# 07_AD9363.net
KiCad netlist of a schematic drawn in Altium Designer
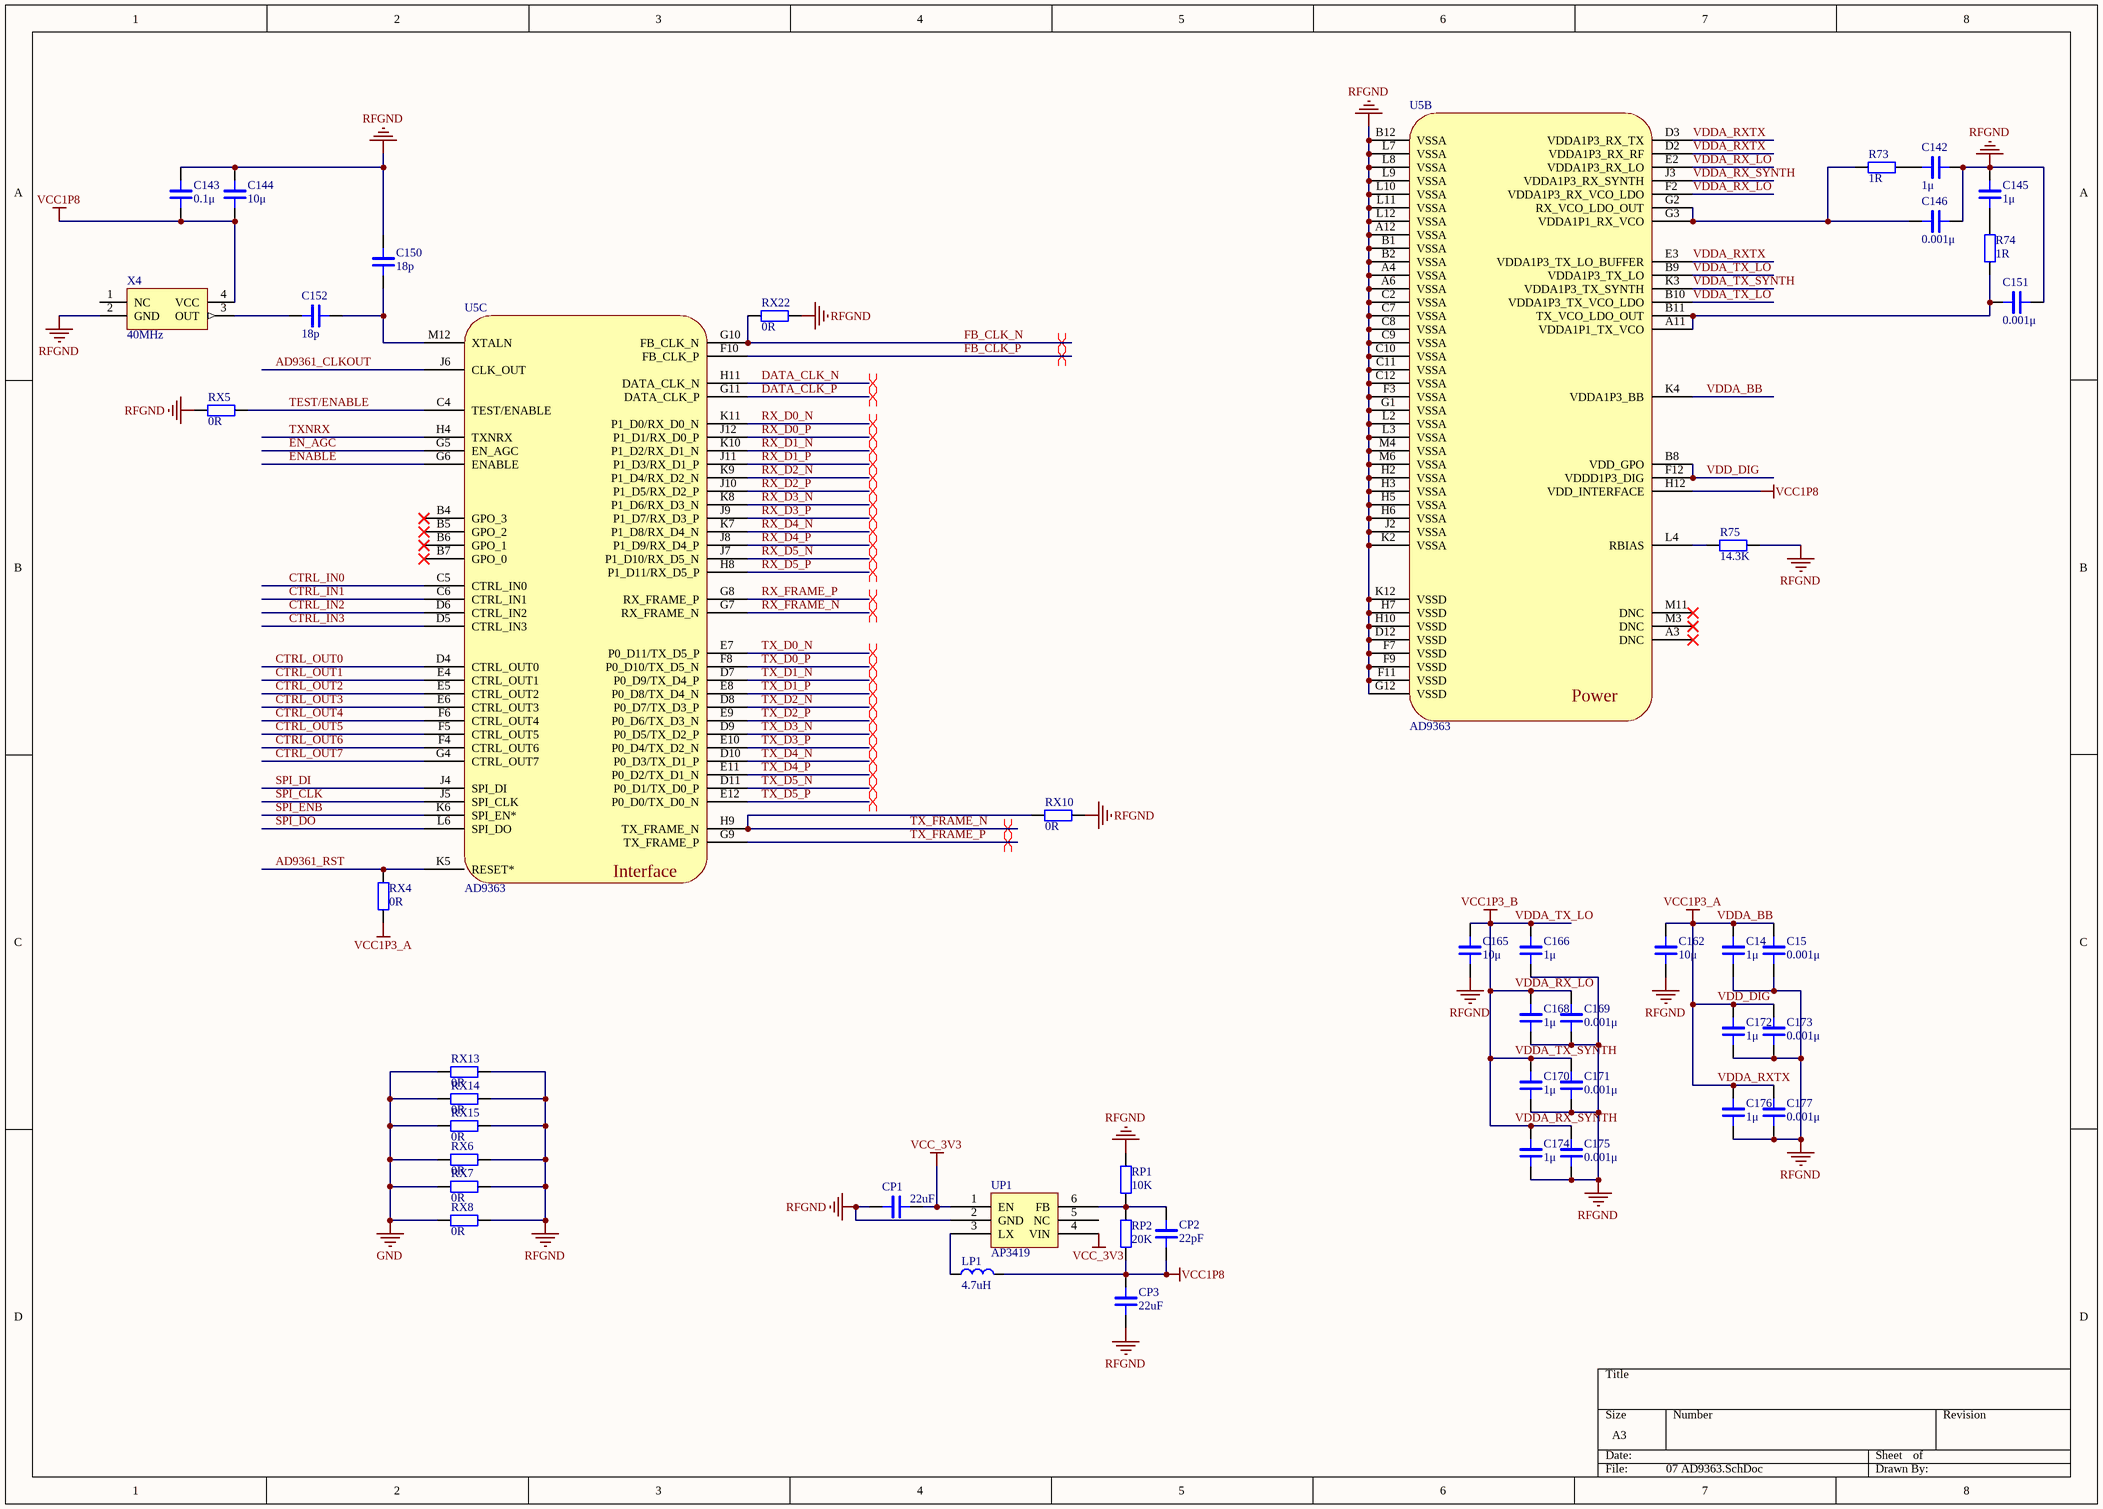
[diagram p0: 07 AD9363.SchDoc]

(export (version "E")
  (design (tool "Eeschema 10.0.6"))
  (components
    (comp (ref "C14")
      (value "1μ")
      (footprint "LC-0402_C")
      (description "Capacitor")
      (libsource (lib "DDR3_xc7z010-clg400") (part "CAP_1"))
    )
    (comp (ref "C15")
      (value "0.001μ")
      (footprint "LC-0402_C")
      (description "Capacitor")
      (libsource (lib "DDR3_xc7z010-clg400") (part "CAP_1"))
    )
    (comp (ref "C142")
      (value "1μ")
      (footprint "LC-0402_C")
      (description "Capacitor")
      (libsource (lib "DDR3_xc7z010-clg400") (part "CAP_2"))
    )
    (comp (ref "C143")
      (value "0.1μ")
      (footprint "LC-0402_C")
      (description "Capacitor")
      (libsource (lib "DDR3_xc7z010-clg400") (part "CAP_2"))
    )
    (comp (ref "C144")
      (value "10μ")
      (footprint "LC-0402_C")
      (description "Capacitor")
      (libsource (lib "DDR3_xc7z010-clg400") (part "CAP_2"))
    )
    (comp (ref "C145")
      (value "1μ")
      (footprint "LC-0402_C")
      (description "Capacitor")
      (libsource (lib "DDR3_xc7z010-clg400") (part "CAP_1"))
    )
    (comp (ref "C146")
      (value "0.001μ")
      (footprint "LC-0402_C")
      (description "Capacitor")
      (libsource (lib "DDR3_xc7z010-clg400") (part "CAP_1"))
    )
    (comp (ref "C150")
      (value "18p")
      (footprint "LC-0402_C")
      (description "Capacitor")
      (libsource (lib "DDR3_xc7z010-clg400") (part "CAP_1"))
    )
    (comp (ref "C151")
      (value "0.001μ")
      (footprint "LC-0402_C")
      (description "Capacitor")
      (libsource (lib "DDR3_xc7z010-clg400") (part "CAP_1"))
    )
    (comp (ref "C152")
      (value "18p")
      (footprint "LC-0402_C")
      (description "Capacitor")
      (libsource (lib "DDR3_xc7z010-clg400") (part "CAP_1"))
    )
    (comp (ref "C162")
      (value "10μ")
      (footprint "LC-0402_C")
      (description "Capacitor")
      (libsource (lib "DDR3_xc7z010-clg400") (part "CAP_1"))
    )
    (comp (ref "C165")
      (value "10μ")
      (footprint "LC-0402_C")
      (description "Capacitor")
      (libsource (lib "DDR3_xc7z010-clg400") (part "CAP_1"))
    )
    (comp (ref "C166")
      (value "1μ")
      (footprint "LC-0402_C")
      (description "Capacitor")
      (libsource (lib "DDR3_xc7z010-clg400") (part "CAP_1"))
    )
    (comp (ref "C168")
      (value "1μ")
      (footprint "LC-0402_C")
      (description "Capacitor")
      (libsource (lib "DDR3_xc7z010-clg400") (part "CAP_1"))
    )
    (comp (ref "C169")
      (value "0.001μ")
      (footprint "LC-0402_C")
      (description "Capacitor")
      (libsource (lib "DDR3_xc7z010-clg400") (part "CAP_1"))
    )
    (comp (ref "C170")
      (value "1μ")
      (footprint "LC-0402_C")
      (description "Capacitor")
      (libsource (lib "DDR3_xc7z010-clg400") (part "CAP_1"))
    )
    (comp (ref "C171")
      (value "0.001μ")
      (footprint "LC-0402_C")
      (description "Capacitor")
      (libsource (lib "DDR3_xc7z010-clg400") (part "CAP_1"))
    )
    (comp (ref "C172")
      (value "1μ")
      (footprint "LC-0402_C")
      (description "Capacitor")
      (libsource (lib "DDR3_xc7z010-clg400") (part "CAP_1"))
    )
    (comp (ref "C173")
      (value "0.001μ")
      (footprint "LC-0402_C")
      (description "Capacitor")
      (libsource (lib "DDR3_xc7z010-clg400") (part "CAP_1"))
    )
    (comp (ref "C174")
      (value "1μ")
      (footprint "LC-0402_C")
      (description "Capacitor")
      (libsource (lib "DDR3_xc7z010-clg400") (part "CAP_1"))
    )
    (comp (ref "C175")
      (value "0.001μ")
      (footprint "LC-0402_C")
      (description "Capacitor")
      (libsource (lib "DDR3_xc7z010-clg400") (part "CAP_1"))
    )
    (comp (ref "C176")
      (value "1μ")
      (footprint "LC-0402_C")
      (description "Capacitor")
      (libsource (lib "DDR3_xc7z010-clg400") (part "CAP_1"))
    )
    (comp (ref "C177")
      (value "0.001μ")
      (footprint "LC-0402_C")
      (description "Capacitor")
      (libsource (lib "DDR3_xc7z010-clg400") (part "CAP_1"))
    )
    (comp (ref "CP1")
      (value "22uF")
      (footprint "LC-0805_C")
      (description "Capacitor")
      (libsource (lib "DDR3_xc7z010-clg400") (part "CAP_1"))
    )
    (comp (ref "CP2")
      (value "22pF")
      (footprint "LC-0402_C")
      (description "Capacitor")
      (libsource (lib "DDR3_xc7z010-clg400") (part "CAP_2"))
    )
    (comp (ref "CP3")
      (value "22uF")
      (footprint "LC-0805_C")
      (description "Capacitor")
      (libsource (lib "DDR3_xc7z010-clg400") (part "CAP_1"))
    )
    (comp (ref "LP1")
      (value "4.7uH")
      (footprint "L1008")
      (description "Inductance")
      (libsource (lib "DDR3_xc7z010-clg400") (part "INDUCTANCE"))
    )
    (comp (ref "R73")
      (value "1R")
      (footprint "LC-0402_R")
      (description "Resistor")
      (libsource (lib "") (part "RES_1_2"))
    )
    (comp (ref "R74")
      (value "1R")
      (footprint "LC-0402_R")
      (description "Resistor")
      (libsource (lib "") (part "RES_1_3"))
    )
    (comp (ref "R75")
      (value "14.3K")
      (footprint "LC-0402_R")
      (description "Resistor")
      (libsource (lib "") (part "RES_1_2"))
    )
    (comp (ref "RP1")
      (value "10K")
      (footprint "LC-0402_R")
      (description "Resistor")
      (libsource (lib "") (part "RES_1_1"))
    )
    (comp (ref "RP2")
      (value "20K")
      (footprint "LC-0402_R")
      (description "Resistor")
      (libsource (lib "") (part "RES_1_1"))
    )
    (comp (ref "RX4")
      (value "0R")
      (footprint "LC-0402_R")
      (description "Resistor")
      (libsource (lib "") (part "RES_1_3"))
    )
    (comp (ref "RX5")
      (value "0R")
      (footprint "LC-0402_R")
      (description "Resistor")
      (libsource (lib "") (part "RES_1_2"))
    )
    (comp (ref "RX6")
      (value "0R")
      (footprint "LC-0603_L")
      (description "Resistor")
      (libsource (lib "DDR3_xc7z010-clg400") (part "RES_1"))
    )
    (comp (ref "RX7")
      (value "0R")
      (footprint "LC-0603_L")
      (description "Resistor")
      (libsource (lib "DDR3_xc7z010-clg400") (part "RES_1"))
    )
    (comp (ref "RX8")
      (value "0R")
      (footprint "LC-0603_L")
      (description "Resistor")
      (libsource (lib "DDR3_xc7z010-clg400") (part "RES_1"))
    )
    (comp (ref "RX10")
      (value "0R")
      (footprint "LC-0402_R")
      (description "Resistor")
      (libsource (lib "DDR3_xc7z010-clg400") (part "RES_1"))
    )
    (comp (ref "RX13")
      (value "0R")
      (footprint "LC-0603_L")
      (description "Resistor")
      (libsource (lib "DDR3_xc7z010-clg400") (part "RES_1"))
    )
    (comp (ref "RX14")
      (value "0R")
      (footprint "LC-0603_L")
      (description "Resistor")
      (libsource (lib "DDR3_xc7z010-clg400") (part "RES_1"))
    )
    (comp (ref "RX15")
      (value "0R")
      (footprint "LC-0603_L")
      (description "Resistor")
      (libsource (lib "DDR3_xc7z010-clg400") (part "RES_1"))
    )
    (comp (ref "RX22")
      (value "0R")
      (footprint "LC-0402_R")
      (description "Resistor")
      (libsource (lib "DDR3_xc7z010-clg400") (part "RES_1"))
    )
    (comp (ref "U5") (value "AD9363") (footprint "AD936X") (libsource (lib "Schlib1") (part "AD9363")))
    (comp (ref "UP1") (value "AP3419") (footprint "AP3419") (libsource (lib "Schlib1") (part "AP3419")))
    (comp (ref "X4")
      (value "40MHz")
      (footprint "OSC-SMD_4P-L3.2-W2.5-BL")
      (description "Oscillator")
      (libsource (lib "DDR3_xc7z010-clg400") (part "XTAL-4"))
    )
  )
  (nets
    (net (code "1") (name "/AD9361_CLKOUT") (class "Default")
      (node (ref "U5") (pin "J6") (pinfunction "CLK_OUT_J6") (pintype "passive"))
    )
    (net (code "2") (name "/AD9361_RST") (class "Default")
      (node (ref "RX4") (pin "1") (pinfunction "1_1") (pintype "passive"))
      (node (ref "U5") (pin "K5") (pinfunction "RESET*_K5") (pintype "passive"))
    )
    (net (code "3") (name "/CTRL_IN0") (class "Default")
      (node (ref "U5") (pin "C5") (pinfunction "CTRL_IN0_C5") (pintype "passive"))
    )
    (net (code "4") (name "/CTRL_IN1") (class "Default")
      (node (ref "U5") (pin "C6") (pinfunction "CTRL_IN1_C6") (pintype "passive"))
    )
    (net (code "5") (name "/CTRL_IN2") (class "Default")
      (node (ref "U5") (pin "D6") (pinfunction "CTRL_IN2_D6") (pintype "passive"))
    )
    (net (code "6") (name "/CTRL_IN3") (class "Default")
      (node (ref "U5") (pin "D5") (pinfunction "CTRL_IN3_D5") (pintype "passive"))
    )
    (net (code "7") (name "/CTRL_OUT0") (class "Default")
      (node (ref "U5") (pin "D4") (pinfunction "CTRL_OUT0_D4") (pintype "passive"))
    )
    (net (code "8") (name "/CTRL_OUT1") (class "Default")
      (node (ref "U5") (pin "E4") (pinfunction "CTRL_OUT1_E4") (pintype "passive"))
    )
    (net (code "9") (name "/CTRL_OUT2") (class "Default")
      (node (ref "U5") (pin "E5") (pinfunction "CTRL_OUT2_E5") (pintype "passive"))
    )
    (net (code "10") (name "/CTRL_OUT3") (class "Default")
      (node (ref "U5") (pin "E6") (pinfunction "CTRL_OUT3_E6") (pintype "passive"))
    )
    (net (code "11") (name "/CTRL_OUT4") (class "Default")
      (node (ref "U5") (pin "F6") (pinfunction "CTRL_OUT4_F6") (pintype "passive"))
    )
    (net (code "12") (name "/CTRL_OUT5") (class "Default")
      (node (ref "U5") (pin "F5") (pinfunction "CTRL_OUT5_F5") (pintype "passive"))
    )
    (net (code "13") (name "/CTRL_OUT6") (class "Default")
      (node (ref "U5") (pin "F4") (pinfunction "CTRL_OUT6_F4") (pintype "passive"))
    )
    (net (code "14") (name "/CTRL_OUT7") (class "Default")
      (node (ref "U5") (pin "G4") (pinfunction "CTRL_OUT7_G4") (pintype "passive"))
    )
    (net (code "15") (name "/DATA_CLK_N") (class "Default")
      (node (ref "U5") (pin "H11") (pinfunction "DATA_CLK_N_H11") (pintype "passive"))
    )
    (net (code "16") (name "/DATA_CLK_P") (class "Default")
      (node (ref "U5") (pin "G11") (pinfunction "DATA_CLK_P_G11") (pintype "passive"))
    )
    (net (code "17") (name "/ENABLE") (class "Default")
      (node (ref "U5") (pin "G6") (pinfunction "ENABLE_G6") (pintype "passive"))
    )
    (net (code "18") (name "/EN_AGC") (class "Default")
      (node (ref "U5") (pin "G5") (pinfunction "EN_AGC_G5") (pintype "passive"))
    )
    (net (code "19") (name "/FB_CLK_N") (class "Default")
      (node (ref "RX22") (pin "2") (pinfunction "2_2") (pintype "passive"))
      (node (ref "U5") (pin "G10") (pinfunction "FB_CLK_N_G10") (pintype "passive"))
    )
    (net (code "20") (name "/FB_CLK_P") (class "Default")
      (node (ref "U5") (pin "F10") (pinfunction "FB_CLK_P_F10") (pintype "passive"))
    )
    (net (code "21") (name "/RX_D0_N") (class "Default")
      (node (ref "U5") (pin "K11") (pinfunction "P1_D0/RX_D0_N_K11") (pintype "passive"))
    )
    (net (code "22") (name "/RX_D0_P") (class "Default")
      (node (ref "U5") (pin "J12") (pinfunction "P1_D1/RX_D0_P_J12") (pintype "passive"))
    )
    (net (code "23") (name "/RX_D1_N") (class "Default")
      (node (ref "U5") (pin "K10") (pinfunction "P1_D2/RX_D1_N_K10") (pintype "passive"))
    )
    (net (code "24") (name "/RX_D1_P") (class "Default")
      (node (ref "U5") (pin "J11") (pinfunction "P1_D3/RX_D1_P_J11") (pintype "passive"))
    )
    (net (code "25") (name "/RX_D2_N") (class "Default")
      (node (ref "U5") (pin "K9") (pinfunction "P1_D4/RX_D2_N_K9") (pintype "passive"))
    )
    (net (code "26") (name "/RX_D2_P") (class "Default")
      (node (ref "U5") (pin "J10") (pinfunction "P1_D5/RX_D2_P_J10") (pintype "passive"))
    )
    (net (code "27") (name "/RX_D3_N") (class "Default")
      (node (ref "U5") (pin "K8") (pinfunction "P1_D6/RX_D3_N_K8") (pintype "passive"))
    )
    (net (code "28") (name "/RX_D3_P") (class "Default")
      (node (ref "U5") (pin "J9") (pinfunction "P1_D7/RX_D3_P_J9") (pintype "passive"))
    )
    (net (code "29") (name "/RX_D4_N") (class "Default")
      (node (ref "U5") (pin "K7") (pinfunction "P1_D8/RX_D4_N_K7") (pintype "passive"))
    )
    (net (code "30") (name "/RX_D4_P") (class "Default")
      (node (ref "U5") (pin "J8") (pinfunction "P1_D9/RX_D4_P_J8") (pintype "passive"))
    )
    (net (code "31") (name "/RX_D5_N") (class "Default")
      (node (ref "U5") (pin "J7") (pinfunction "P1_D10/RX_D5_N_J7") (pintype "passive"))
    )
    (net (code "32") (name "/RX_D5_P") (class "Default")
      (node (ref "U5") (pin "H8") (pinfunction "P1_D11/RX_D5_P_H8") (pintype "passive"))
    )
    (net (code "33") (name "/RX_FRAME_N") (class "Default")
      (node (ref "U5") (pin "G7") (pinfunction "RX_FRAME_N_G7") (pintype "passive"))
    )
    (net (code "34") (name "/RX_FRAME_P") (class "Default")
      (node (ref "U5") (pin "G8") (pinfunction "RX_FRAME_P_G8") (pintype "passive"))
    )
    (net (code "35") (name "/SPI_CLK") (class "Default")
      (node (ref "U5") (pin "J5") (pinfunction "SPI_CLK_J5") (pintype "passive"))
    )
    (net (code "36") (name "/SPI_DI") (class "Default")
      (node (ref "U5") (pin "J4") (pinfunction "SPI_DI_J4") (pintype "passive"))
    )
    (net (code "37") (name "/SPI_DO") (class "Default")
      (node (ref "U5") (pin "L6") (pinfunction "SPI_DO_L6") (pintype "passive"))
    )
    (net (code "38") (name "/SPI_ENB") (class "Default")
      (node (ref "U5") (pin "K6") (pinfunction "SPI_EN*_K6") (pintype "passive"))
    )
    (net (code "39") (name "/TEST{slash}ENABLE") (class "Default")
      (node (ref "RX5") (pin "2") (pinfunction "2_2") (pintype "passive"))
      (node (ref "U5") (pin "C4") (pinfunction "TEST/ENABLE_C4") (pintype "passive"))
    )
    (net (code "40") (name "/TXNRX") (class "Default")
      (node (ref "U5") (pin "H4") (pinfunction "TXNRX_H4") (pintype "passive"))
    )
    (net (code "41") (name "/TX_D0_N") (class "Default")
      (node (ref "U5") (pin "E7") (pinfunction "P0_D11/TX_D5_P_E7") (pintype "passive"))
    )
    (net (code "42") (name "/TX_D0_P") (class "Default")
      (node (ref "U5") (pin "F8") (pinfunction "P0_D10/TX_D5_N_F8") (pintype "passive"))
    )
    (net (code "43") (name "/TX_D1_N") (class "Default")
      (node (ref "U5") (pin "D7") (pinfunction "P0_D9/TX_D4_P_D7") (pintype "passive"))
    )
    (net (code "44") (name "/TX_D1_P") (class "Default")
      (node (ref "U5") (pin "E8") (pinfunction "P0_D8/TX_D4_N_E8") (pintype "passive"))
    )
    (net (code "45") (name "/TX_D2_N") (class "Default")
      (node (ref "U5") (pin "D8") (pinfunction "P0_D7/TX_D3_P_D8") (pintype "passive"))
    )
    (net (code "46") (name "/TX_D2_P") (class "Default")
      (node (ref "U5") (pin "E9") (pinfunction "P0_D6/TX_D3_N_E9") (pintype "passive"))
    )
    (net (code "47") (name "/TX_D3_N") (class "Default")
      (node (ref "U5") (pin "D9") (pinfunction "P0_D5/TX_D2_P_D9") (pintype "passive"))
    )
    (net (code "48") (name "/TX_D3_P") (class "Default")
      (node (ref "U5") (pin "E10") (pinfunction "P0_D4/TX_D2_N_E10") (pintype "passive"))
    )
    (net (code "49") (name "/TX_D4_N") (class "Default")
      (node (ref "U5") (pin "D10") (pinfunction "P0_D3/TX_D1_P_D10") (pintype "passive"))
    )
    (net (code "50") (name "/TX_D4_P") (class "Default")
      (node (ref "U5") (pin "E11") (pinfunction "P0_D2/TX_D1_N_E11") (pintype "passive"))
    )
    (net (code "51") (name "/TX_D5_N") (class "Default")
      (node (ref "U5") (pin "D11") (pinfunction "P0_D1/TX_D0_P_D11") (pintype "passive"))
    )
    (net (code "52") (name "/TX_D5_P") (class "Default")
      (node (ref "U5") (pin "E12") (pinfunction "P0_D0/TX_D0_N_E12") (pintype "passive"))
    )
    (net (code "53") (name "/TX_FRAME_N") (class "Default")
      (node (ref "RX10") (pin "2") (pinfunction "2_2") (pintype "passive"))
      (node (ref "U5") (pin "H9") (pinfunction "TX_FRAME_N_H9") (pintype "passive"))
    )
    (net (code "54") (name "/TX_FRAME_P") (class "Default")
      (node (ref "U5") (pin "G9") (pinfunction "TX_FRAME_P_G9") (pintype "passive"))
    )
    (net (code "55") (name "GND") (class "Default")
      (node (ref "RX13") (pin "2") (pinfunction "2_2") (pintype "passive"))
      (node (ref "RX14") (pin "2") (pinfunction "2_2") (pintype "passive"))
      (node (ref "RX15") (pin "2") (pinfunction "2_2") (pintype "passive"))
      (node (ref "RX6") (pin "2") (pinfunction "2_2") (pintype "passive"))
      (node (ref "RX7") (pin "2") (pinfunction "2_2") (pintype "passive"))
      (node (ref "RX8") (pin "2") (pinfunction "2_2") (pintype "passive"))
    )
    (net (code "56") (name "Net-(C142-Pad1)") (class "Default")
      (node (ref "C142") (pin "1") (pinfunction "1_1") (pintype "passive"))
      (node (ref "R73") (pin "2") (pinfunction "2_2") (pintype "passive"))
    )
    (net (code "57") (name "Net-(C145-Pad2)") (class "Default")
      (node (ref "C145") (pin "2") (pinfunction "2_2") (pintype "passive"))
      (node (ref "R74") (pin "1") (pinfunction "1_1") (pintype "passive"))
    )
    (net (code "58") (name "Net-(U5B-RBIAS)") (class "Default")
      (node (ref "R75") (pin "1") (pinfunction "1_1") (pintype "passive"))
      (node (ref "U5") (pin "L4") (pinfunction "RBIAS_L4") (pintype "passive"))
    )
    (net (code "59") (name "Net-(U5B-RX_VCO_LDO_OUT)") (class "Default")
      (node (ref "C146") (pin "2") (pinfunction "2_2") (pintype "passive"))
      (node (ref "R73") (pin "1") (pinfunction "1_1") (pintype "passive"))
      (node (ref "U5") (pin "G2") (pinfunction "RX_VCO_LDO_OUT_G2") (pintype "passive"))
      (node (ref "U5") (pin "G3") (pinfunction "VDDA1P1_RX_VCO_G3") (pintype "passive"))
    )
    (net (code "60") (name "Net-(U5B-TX_VCO_LDO_OUT)") (class "Default")
      (node (ref "C151") (pin "2") (pinfunction "2_2") (pintype "passive"))
      (node (ref "R74") (pin "2") (pinfunction "2_2") (pintype "passive"))
      (node (ref "U5") (pin "A11") (pinfunction "VDDA1P1_TX_VCO_A11") (pintype "passive"))
      (node (ref "U5") (pin "B11") (pinfunction "TX_VCO_LDO_OUT_B11") (pintype "passive"))
    )
    (net (code "61") (name "Net-(U5C-XTALN)") (class "Default")
      (node (ref "C150") (pin "2") (pinfunction "2_2") (pintype "passive"))
      (node (ref "C152") (pin "1") (pinfunction "1_1") (pintype "passive"))
      (node (ref "U5") (pin "M12") (pinfunction "XTALN_M12") (pintype "passive"))
    )
    (net (code "62") (name "Net-(UP1-FB)") (class "Default")
      (node (ref "CP2") (pin "2") (pinfunction "2_2") (pintype "passive"))
      (node (ref "RP1") (pin "1") (pinfunction "1_1") (pintype "passive"))
      (node (ref "RP2") (pin "2") (pinfunction "2_2") (pintype "passive"))
      (node (ref "UP1") (pin "6") (pinfunction "FB_6") (pintype "passive"))
    )
    (net (code "63") (name "Net-(UP1-LX)") (class "Default")
      (node (ref "LP1") (pin "1") (pinfunction "1_1") (pintype "passive"))
      (node (ref "UP1") (pin "3") (pinfunction "LX_3") (pintype "passive"))
    )
    (net (code "64") (name "Net-(X4-OUT)") (class "Default")
      (node (ref "C152") (pin "2") (pinfunction "2_2") (pintype "passive"))
      (node (ref "X4") (pin "3") (pinfunction "OUT_3") (pintype "output"))
    )
    (net (code "65") (name "RFGND") (class "Default")
      (node (ref "C14") (pin "2") (pinfunction "2_2") (pintype "passive"))
      (node (ref "C142") (pin "2") (pinfunction "2_2") (pintype "passive"))
      (node (ref "C143") (pin "1") (pinfunction "1_1") (pintype "passive"))
      (node (ref "C144") (pin "1") (pinfunction "1_1") (pintype "passive"))
      (node (ref "C145") (pin "1") (pinfunction "1_1") (pintype "passive"))
      (node (ref "C146") (pin "1") (pinfunction "1_1") (pintype "passive"))
      (node (ref "C15") (pin "2") (pinfunction "2_2") (pintype "passive"))
      (node (ref "C150") (pin "1") (pinfunction "1_1") (pintype "passive"))
      (node (ref "C151") (pin "1") (pinfunction "1_1") (pintype "passive"))
      (node (ref "C162") (pin "2") (pinfunction "2_2") (pintype "passive"))
      (node (ref "C165") (pin "2") (pinfunction "2_2") (pintype "passive"))
      (node (ref "C166") (pin "2") (pinfunction "2_2") (pintype "passive"))
      (node (ref "C168") (pin "2") (pinfunction "2_2") (pintype "passive"))
      (node (ref "C169") (pin "2") (pinfunction "2_2") (pintype "passive"))
      (node (ref "C170") (pin "2") (pinfunction "2_2") (pintype "passive"))
      (node (ref "C171") (pin "2") (pinfunction "2_2") (pintype "passive"))
      (node (ref "C172") (pin "2") (pinfunction "2_2") (pintype "passive"))
      (node (ref "C173") (pin "2") (pinfunction "2_2") (pintype "passive"))
      (node (ref "C174") (pin "2") (pinfunction "2_2") (pintype "passive"))
      (node (ref "C175") (pin "2") (pinfunction "2_2") (pintype "passive"))
      (node (ref "C176") (pin "2") (pinfunction "2_2") (pintype "passive"))
      (node (ref "C177") (pin "2") (pinfunction "2_2") (pintype "passive"))
      (node (ref "CP1") (pin "1") (pinfunction "1_1") (pintype "passive"))
      (node (ref "CP3") (pin "1") (pinfunction "1_1") (pintype "passive"))
      (node (ref "R75") (pin "2") (pinfunction "2_2") (pintype "passive"))
      (node (ref "RP1") (pin "2") (pinfunction "2_2") (pintype "passive"))
      (node (ref "RX10") (pin "1") (pinfunction "1_1") (pintype "passive"))
      (node (ref "RX13") (pin "1") (pinfunction "1_1") (pintype "passive"))
      (node (ref "RX14") (pin "1") (pinfunction "1_1") (pintype "passive"))
      (node (ref "RX15") (pin "1") (pinfunction "1_1") (pintype "passive"))
      (node (ref "RX22") (pin "1") (pinfunction "1_1") (pintype "passive"))
      (node (ref "RX5") (pin "1") (pinfunction "1_1") (pintype "passive"))
      (node (ref "RX6") (pin "1") (pinfunction "1_1") (pintype "passive"))
      (node (ref "RX7") (pin "1") (pinfunction "1_1") (pintype "passive"))
      (node (ref "RX8") (pin "1") (pinfunction "1_1") (pintype "passive"))
      (node (ref "U5") (pin "A12") (pinfunction "VSSA_A12") (pintype "passive"))
      (node (ref "U5") (pin "A4") (pinfunction "VSSA_A4") (pintype "passive"))
      (node (ref "U5") (pin "A6") (pinfunction "VSSA_A6") (pintype "passive"))
      (node (ref "U5") (pin "B1") (pinfunction "VSSA_B1") (pintype "passive"))
      (node (ref "U5") (pin "B12") (pinfunction "VSSA_B12") (pintype "passive"))
      (node (ref "U5") (pin "B2") (pinfunction "VSSA_B2") (pintype "passive"))
      (node (ref "U5") (pin "C10") (pinfunction "VSSA_C10") (pintype "passive"))
      (node (ref "U5") (pin "C11") (pinfunction "VSSA_C11") (pintype "passive"))
      (node (ref "U5") (pin "C12") (pinfunction "VSSA_C12") (pintype "passive"))
      (node (ref "U5") (pin "C2") (pinfunction "VSSA_C2") (pintype "passive"))
      (node (ref "U5") (pin "C7") (pinfunction "VSSA_C7") (pintype "passive"))
      (node (ref "U5") (pin "C8") (pinfunction "VSSA_C8") (pintype "passive"))
      (node (ref "U5") (pin "C9") (pinfunction "VSSA_C9") (pintype "passive"))
      (node (ref "U5") (pin "D12") (pinfunction "VSSD_D12") (pintype "passive"))
      (node (ref "U5") (pin "F11") (pinfunction "VSSD_F11") (pintype "passive"))
      (node (ref "U5") (pin "F3") (pinfunction "VSSA_F3") (pintype "passive"))
      (node (ref "U5") (pin "F7") (pinfunction "VSSD_F7") (pintype "passive"))
      (node (ref "U5") (pin "F9") (pinfunction "VSSD_F9") (pintype "passive"))
      (node (ref "U5") (pin "G1") (pinfunction "VSSA_G1") (pintype "passive"))
      (node (ref "U5") (pin "G12") (pinfunction "VSSD_G12") (pintype "passive"))
      (node (ref "U5") (pin "H10") (pinfunction "VSSD_H10") (pintype "passive"))
      (node (ref "U5") (pin "H2") (pinfunction "VSSA_H2") (pintype "passive"))
      (node (ref "U5") (pin "H3") (pinfunction "VSSA_H3") (pintype "passive"))
      (node (ref "U5") (pin "H5") (pinfunction "VSSA_H5") (pintype "passive"))
      (node (ref "U5") (pin "H6") (pinfunction "VSSA_H6") (pintype "passive"))
      (node (ref "U5") (pin "H7") (pinfunction "VSSD_H7") (pintype "passive"))
      (node (ref "U5") (pin "J2") (pinfunction "VSSA_J2") (pintype "passive"))
      (node (ref "U5") (pin "K12") (pinfunction "VSSD_K12") (pintype "passive"))
      (node (ref "U5") (pin "K2") (pinfunction "VSSA_K2") (pintype "passive"))
      (node (ref "U5") (pin "L10") (pinfunction "VSSA_L10") (pintype "passive"))
      (node (ref "U5") (pin "L11") (pinfunction "VSSA_L11") (pintype "passive"))
      (node (ref "U5") (pin "L12") (pinfunction "VSSA_L12") (pintype "passive"))
      (node (ref "U5") (pin "L2") (pinfunction "VSSA_L2") (pintype "passive"))
      (node (ref "U5") (pin "L3") (pinfunction "VSSA_L3") (pintype "passive"))
      (node (ref "U5") (pin "L7") (pinfunction "VSSA_L7") (pintype "passive"))
      (node (ref "U5") (pin "L8") (pinfunction "VSSA_L8") (pintype "passive"))
      (node (ref "U5") (pin "L9") (pinfunction "VSSA_L9") (pintype "passive"))
      (node (ref "U5") (pin "M4") (pinfunction "VSSA_M4") (pintype "passive"))
      (node (ref "U5") (pin "M6") (pinfunction "VSSA_M6") (pintype "passive"))
      (node (ref "UP1") (pin "2") (pinfunction "GND_2") (pintype "passive"))
      (node (ref "X4") (pin "2") (pinfunction "GND_2") (pintype "power_in"))
    )
    (net (code "66") (name "VCC1P3_A") (class "Default")
      (node (ref "C14") (pin "1") (pinfunction "1_1") (pintype "passive"))
      (node (ref "C15") (pin "1") (pinfunction "1_1") (pintype "passive"))
      (node (ref "C162") (pin "1") (pinfunction "1_1") (pintype "passive"))
      (node (ref "C172") (pin "1") (pinfunction "1_1") (pintype "passive"))
      (node (ref "C173") (pin "1") (pinfunction "1_1") (pintype "passive"))
      (node (ref "C176") (pin "1") (pinfunction "1_1") (pintype "passive"))
      (node (ref "C177") (pin "1") (pinfunction "1_1") (pintype "passive"))
      (node (ref "RX4") (pin "2") (pinfunction "2_2") (pintype "passive"))
      (node (ref "U5") (pin "B8") (pinfunction "VDD_GPO_B8") (pintype "passive"))
      (node (ref "U5") (pin "D2") (pinfunction "VDDA1P3_RX_RF_D2") (pintype "passive"))
      (node (ref "U5") (pin "D3") (pinfunction "VDDA1P3_RX_TX_D3") (pintype "passive"))
      (node (ref "U5") (pin "E3") (pinfunction "VDDA1P3_TX_LO_BUFFER_E3") (pintype "passive"))
      (node (ref "U5") (pin "F12") (pinfunction "VDDD1P3_DIG_F12") (pintype "passive"))
      (node (ref "U5") (pin "K4") (pinfunction "VDDA1P3_BB_K4") (pintype "passive"))
    )
    (net (code "67") (name "VCC1P3_B") (class "Default")
      (node (ref "C165") (pin "1") (pinfunction "1_1") (pintype "passive"))
      (node (ref "C166") (pin "1") (pinfunction "1_1") (pintype "passive"))
      (node (ref "C168") (pin "1") (pinfunction "1_1") (pintype "passive"))
      (node (ref "C169") (pin "1") (pinfunction "1_1") (pintype "passive"))
      (node (ref "C170") (pin "1") (pinfunction "1_1") (pintype "passive"))
      (node (ref "C171") (pin "1") (pinfunction "1_1") (pintype "passive"))
      (node (ref "C174") (pin "1") (pinfunction "1_1") (pintype "passive"))
      (node (ref "C175") (pin "1") (pinfunction "1_1") (pintype "passive"))
      (node (ref "U5") (pin "B10") (pinfunction "VDDA1P3_TX_VCO_LDO_B10") (pintype "passive"))
      (node (ref "U5") (pin "B9") (pinfunction "VDDA1P3_TX_LO_B9") (pintype "passive"))
      (node (ref "U5") (pin "E2") (pinfunction "VDDA1P3_RX_LO_E2") (pintype "passive"))
      (node (ref "U5") (pin "F2") (pinfunction "VDDA1P3_RX_VCO_LDO_F2") (pintype "passive"))
      (node (ref "U5") (pin "J3") (pinfunction "VDDA1P3_RX_SYNTH_J3") (pintype "passive"))
      (node (ref "U5") (pin "K3") (pinfunction "VDDA1P3_TX_SYNTH_K3") (pintype "passive"))
    )
    (net (code "68") (name "VCC1P8") (class "Default")
      (node (ref "C143") (pin "2") (pinfunction "2_2") (pintype "passive"))
      (node (ref "C144") (pin "2") (pinfunction "2_2") (pintype "passive"))
      (node (ref "CP2") (pin "1") (pinfunction "1_1") (pintype "passive"))
      (node (ref "CP3") (pin "2") (pinfunction "2_2") (pintype "passive"))
      (node (ref "LP1") (pin "2") (pinfunction "2_2") (pintype "passive"))
      (node (ref "RP2") (pin "1") (pinfunction "1_1") (pintype "passive"))
      (node (ref "U5") (pin "H12") (pinfunction "VDD_INTERFACE_H12") (pintype "passive"))
      (node (ref "X4") (pin "4") (pinfunction "VCC_4") (pintype "power_in"))
    )
    (net (code "69") (name "VCC_3V3") (class "Default")
      (node (ref "CP1") (pin "2") (pinfunction "2_2") (pintype "passive"))
      (node (ref "UP1") (pin "1") (pinfunction "EN_1") (pintype "passive"))
      (node (ref "UP1") (pin "4") (pinfunction "VIN_4") (pintype "passive"))
    )
    (net (code "70") (name "unconnected-(U5B-DNC-PadA3)") (class "Default")
      (node (ref "U5") (pin "A3") (pinfunction "DNC_A3") (pintype "passive+no_connect"))
    )
    (net (code "71") (name "unconnected-(U5B-DNC-PadM3)") (class "Default")
      (node (ref "U5") (pin "M3") (pinfunction "DNC_M3") (pintype "passive+no_connect"))
    )
    (net (code "72") (name "unconnected-(U5B-DNC-PadM11)") (class "Default")
      (node (ref "U5") (pin "M11") (pinfunction "DNC_M11") (pintype "passive+no_connect"))
    )
    (net (code "73") (name "unconnected-(U5C-GPO_0-PadB7)") (class "Default")
      (node (ref "U5") (pin "B7") (pinfunction "GPO_0_B7") (pintype "passive+no_connect"))
    )
    (net (code "74") (name "unconnected-(U5C-GPO_1-PadB6)") (class "Default")
      (node (ref "U5") (pin "B6") (pinfunction "GPO_1_B6") (pintype "passive+no_connect"))
    )
    (net (code "75") (name "unconnected-(U5C-GPO_2-PadB5)") (class "Default")
      (node (ref "U5") (pin "B5") (pinfunction "GPO_2_B5") (pintype "passive+no_connect"))
    )
    (net (code "76") (name "unconnected-(U5C-GPO_3-PadB4)") (class "Default")
      (node (ref "U5") (pin "B4") (pinfunction "GPO_3_B4") (pintype "passive+no_connect"))
    )
    (net (code "77") (name "unconnected-(UP1-NC-Pad5)") (class "Default")
      (node (ref "UP1") (pin "5") (pinfunction "NC_5") (pintype "passive"))
    )
    (net (code "78") (name "unconnected-(X4-NC-Pad1)") (class "Default")
      (node (ref "X4") (pin "1") (pinfunction "NC_1") (pintype "passive"))
    )
  )
)
